# Power1.net
KiCad netlist of a schematic drawn in Altium Designer
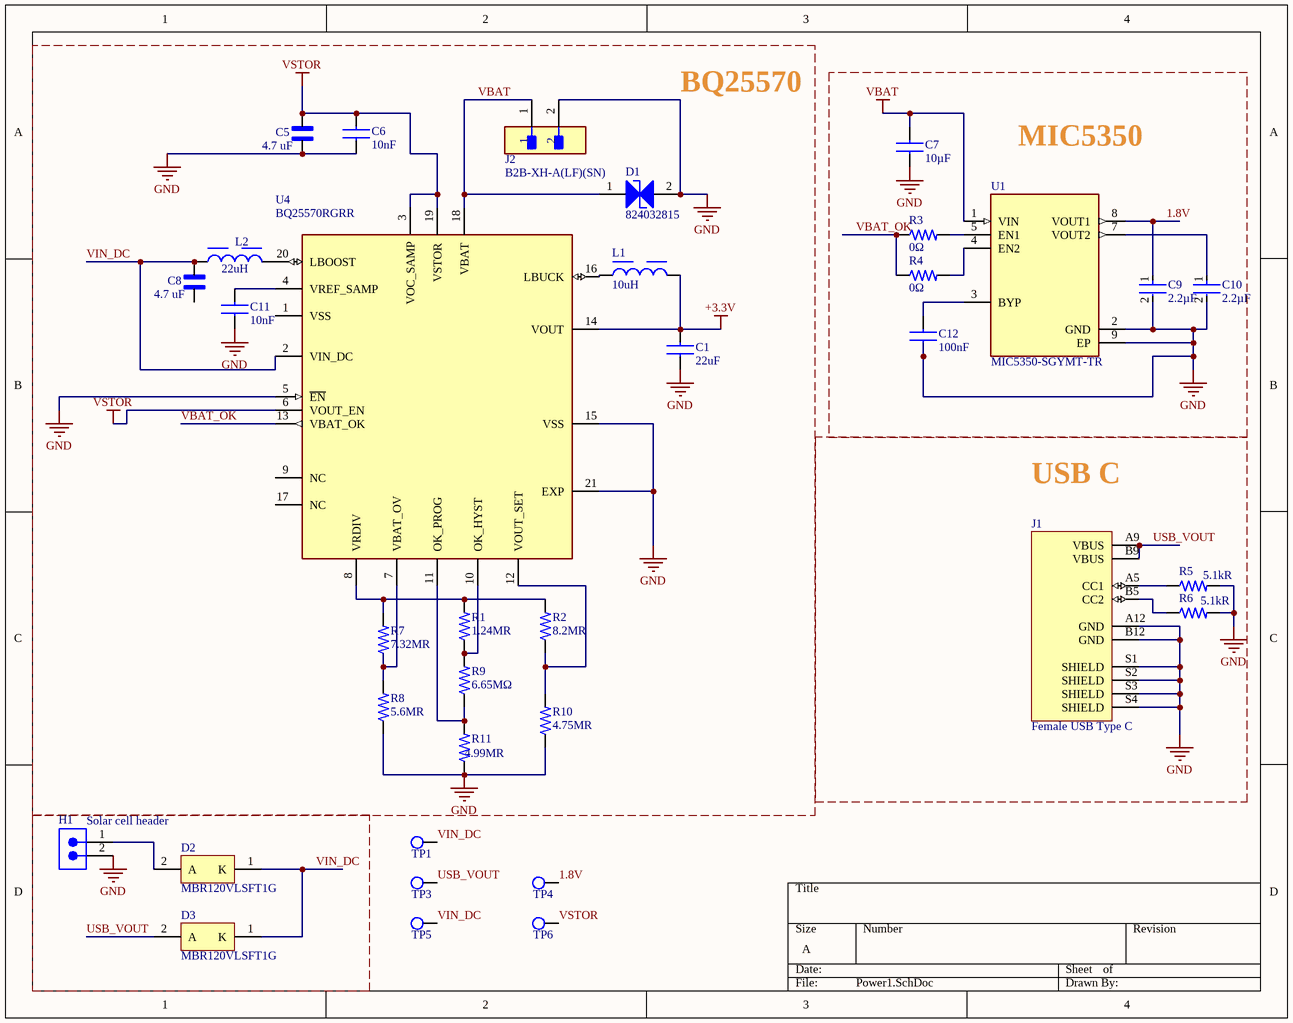
[diagram p0: Power1.SchDoc]

(export (version "E")
  (design (tool "Eeschema 10.0.6"))
  (components
    (comp (ref "C1")
      (value "22uF")
      (footprint "CAP_0603_1MM")
      (description "CAP CER 22UF 10V X5R 0603")
      (fields
        (field (name "MANUFACTURER") "Murata")
        (field (name "MANUFACTURER PART NUMBER") "GRM188R61A226ME15D")
      )
      (libsource (lib "LPEDT_Components") (part "GRM188R61A226ME15D"))
    )
    (comp (ref "C5")
      (value "4.7 uF")
      (footprint "CAPC1608X90N")
      (description "4.7 ÂµF Â±10% 16V Ceramic Capacitor X5R 0603 (1608 Metric)")
      (fields (field (name "MF") "Samsung Electro-Mechanics") (field (name "MP") "CL10A475KO8NNNC"))
      (libsource (lib "LPEDT_Components") (part "CL10A475KO8NNNC"))
    )
    (comp (ref "C6")
      (value "10nF")
      (footprint "CAP_0603_1MM")
      (description "Multilayer Ceramic Capacitors MLCC - SMD/SMT 16V 0.01uF X7R 0603 10% AEC-Q200")
      (fields
        (field (name "MANUFACTURER") "KEMET")
        (field (name "MANUFACTURER PART NUMBER") "C0603C103K4RECAUTO")
      )
      (libsource (lib "LPEDT_Components") (part "CAP 10nF 0603"))
    )
    (comp (ref "C7")
      (value "10µF")
      (footprint "CAP_0603_1MM")
      (description "10V 10uF X7R ±10% 0603 Multilayer Ceramic Capacitors MLCC - SMD/SMT ROHS")
      (fields
        (field (name "MANUFACTURER") "Murata")
        (field (name "MANUFACTURER PART NUMBER") "GRM188Z71A106KA73D")
      )
      (libsource (lib "LPEDT_Components") (part "CAP 10uF 0603"))
    )
    (comp (ref "C8")
      (value "4.7 uF")
      (footprint "CAPC1608X90N")
      (description "4.7 ÂµF Â±10% 16V Ceramic Capacitor X5R 0603 (1608 Metric)")
      (fields (field (name "MF") "Samsung Electro-Mechanics") (field (name "MP") "CL10A475KO8NNNC"))
      (libsource (lib "LPEDT_Components") (part "CL10A475KO8NNNC"))
    )
    (comp (ref "C9")
      (value "2.2µF")
      (footprint "CAP_0603_1MM")
      (description "10V 2.2uF X7R ±10% 0603 Multilayer Ceramic Capacitors MLCC - SMD/SMT ROHS")
      (fields
        (field (name "MANUFACTURER") "Samsung Electro-Mechanics")
        (field (name "MANUFACTURER PART NUMBER") "CL10B225KP8NNNC")
      )
      (libsource (lib "LPEDT_Components") (part "CAP 2.2uF 0603"))
    )
    (comp (ref "C10")
      (value "2.2µF")
      (footprint "CAP_0603_1MM")
      (description "10V 2.2uF X7R ±10% 0603 Multilayer Ceramic Capacitors MLCC - SMD/SMT ROHS")
      (fields
        (field (name "MANUFACTURER") "Samsung Electro-Mechanics")
        (field (name "MANUFACTURER PART NUMBER") "CL10B225KP8NNNC")
      )
      (libsource (lib "LPEDT_Components") (part "CAP 2.2uF 0603"))
    )
    (comp (ref "C11")
      (value "10nF")
      (footprint "CAP_0603_1MM")
      (description "Multilayer Ceramic Capacitors MLCC - SMD/SMT 16V 0.01uF X7R 0603 10% AEC-Q200")
      (fields
        (field (name "MANUFACTURER") "KEMET")
        (field (name "MANUFACTURER PART NUMBER") "C0603C103K4RECAUTO")
      )
      (libsource (lib "LPEDT_Components") (part "CAP 10nF 0603"))
    )
    (comp (ref "C12")
      (value "100nF")
      (footprint "CAP_0603_1MM")
      (description "0603 0.1 uF 10 V ±10% Tolerance X7R SMT Multilayer Ceramic Chip Capacitor")
      (fields
        (field (name "MANUFACTURER") "Vishay")
        (field (name "MANUFACTURER PART NUMBER") "VJ0603Y104KXQCW1BC")
      )
      (libsource (lib "LPEDT_Components") (part "CAP 0.1uF 0603"))
    )
    (comp (ref "D1")
      (value "824032815")
      (footprint "WE-TVS_DFN1610-2L")
      (description "824032815 Tvs Diode, Bidir, 5V, Dfn1610 Rohs Compliant: Yes ¦Wurth Elektronik 824032815")
      (libsource (lib "LPEDT_Components") (part "TVS Diode ESD Protection"))
    )
    (comp (ref "D2")
      (value "MBR120VLSFT1G")
      (footprint "ONSC-SOD-123FL-2-498-01_V")
      (description "Schottky Power Rectifier, 2-Pin SOD-123, Pb-Free, Tape and Reel")
      (fields (field (name "MANUFACTURER") "On Semiconductor"))
      (libsource (lib "LPEDT_Components") (part "Diode Schottky"))
    )
    (comp (ref "D3")
      (value "MBR120VLSFT1G")
      (footprint "ONSC-SOD-123FL-2-498-01_V")
      (description "Schottky Power Rectifier, 2-Pin SOD-123, Pb-Free, Tape and Reel")
      (fields (field (name "MANUFACTURER") "On Semiconductor"))
      (libsource (lib "LPEDT_Components") (part "Diode Schottky"))
    )
    (comp (ref "H1")
      (value "Solar cell header")
      (footprint "2-PIN_MALE_HEADER_01-IN")
      (description "CONN HEADER VERT 2POS 2.54MM")
      (fields
        (field (name "MANUFACTURER") "Sullins")
        (field (name "MANUFACTURER PART NUMBER") "PRPC002SAAN-RC")
      )
      (libsource (lib "LPEDT_Components") (part "SOLAR_CELL"))
    )
    (comp (ref "J1")
      (value "Female USB Type C")
      (footprint "GCT_USB4125-GF-A_REVA2")
      (fields (field (name "MANUFACTURER PART NUMBER") "USB4125-GF-A_REVA2"))
      (libsource (lib "LPEDT_Components") (part "USB-C Power Connector"))
    )
    (comp (ref "J2")
      (value "B2B-XH-A(LF)(SN)")
      (footprint "FP-B2B-XH-A_LF_SN-MFG")
      (description "CONN HEADER VERT 2POS 2.5MM")
      (libsource (lib "LPEDT_Components") (part "CMP-2000-05888-3"))
    )
    (comp (ref "L1")
      (value "10uH")
      (footprint "WE-TPC_2813")
      (description "10 µH Shielded Drum Core, Wirewound Inductor 650 mA 470mOhm Max Nonstandard")
      (fields (field (name "TOLERANCE") "30%"))
      (libsource (lib "LPEDT_Components") (part "CMP-0227-00077-3"))
    )
    (comp (ref "L2")
      (value "22uH")
      (footprint "WE-TPC_3816")
      (description "22 µH Shielded Drum Core, Wirewound Inductor 510 mA 450mOhm Max Nonstandard")
      (fields (field (name "TOLERANCE") "30%"))
      (libsource (lib "LPEDT_Components") (part "CMP-0227-00346-4"))
    )
    (comp (ref "R1")
      (value "1.24MR")
      (footprint "RES_0603_1608X06")
      (fields
        (field (name "MANUFACTURER") "Yageo")
        (field (name "MANUFACTURER PART NUMBER") "RC0603FR-071M24L")
        (field (name "TOLERANCE") "1%")
      )
      (libsource (lib "LPEDT_Component_Lib") (part "RES 1.24M 0603"))
    )
    (comp (ref "R2")
      (value "8.2MR")
      (footprint "RES_0603_1608X06")
      (fields
        (field (name "MANUFACTURER") "Yageo")
        (field (name "MANUFACTURER PART NUMBER") "RC0603JR-078M2L")
        (field (name "TOLERANCE") "5%")
      )
      (libsource (lib "LPEDT_Components") (part "RES 8.2M 0603"))
    )
    (comp (ref "R3")
      (value "0Ω")
      (footprint "RES_0603_1608X06")
      (description "GENERAL PURPOSE CHIP RESISTOR Metal Glaze/thick Film, 0.1W, 0ohm, Surface Mount, 0603")
      (fields
        (field (name "MANUFACTURER") "Yageo Group")
        (field (name "MANUFACTURER PART NUMBER") "RC0603JR-070RL")
      )
      (libsource (lib "LPEDT_Component_Lib") (part "RES 0R 0603"))
    )
    (comp (ref "R4")
      (value "0Ω")
      (footprint "RES_0603_1608X06")
      (description "GENERAL PURPOSE CHIP RESISTOR Metal Glaze/thick Film, 0.1W, 0ohm, Surface Mount, 0603")
      (fields
        (field (name "MANUFACTURER") "Yageo Group")
        (field (name "MANUFACTURER PART NUMBER") "RC0603JR-070RL")
      )
      (libsource (lib "LPEDT_Component_Lib") (part "RES 0R 0603"))
    )
    (comp (ref "R5")
      (value "5.1kR")
      (footprint "RES_0603_1608X06")
      (fields
        (field (name "MANUFACTURER") "Yageo")
        (field (name "MANUFACTURER PART NUMBER") "RC0603FR-075K1L")
        (field (name "TOLERANCE") "1%")
      )
      (libsource (lib "LPEDT_Component_Lib") (part "RES 5.1K 0603"))
    )
    (comp (ref "R6")
      (value "5.1kR")
      (footprint "RES_0603_1608X06")
      (fields
        (field (name "MANUFACTURER") "Yageo")
        (field (name "MANUFACTURER PART NUMBER") "RC0603FR-075K1L")
        (field (name "TOLERANCE") "1%")
      )
      (libsource (lib "LPEDT_Component_Lib") (part "RES 5.1K 0603"))
    )
    (comp (ref "R7")
      (value "7.32MR")
      (footprint "RES_0603_1608X06")
      (fields
        (field (name "MANUFACTURER") "Yageo")
        (field (name "MANUFACTURER PART NUMBER") "RC0402FR-077M32L")
        (field (name "TOLERANCE") "1%")
      )
      (libsource (lib "LPEDT_Component_Lib") (part "RES 7.32M 0603"))
    )
    (comp (ref "R8")
      (value "5.6MR")
      (footprint "RES_0603_1608X06")
      (fields
        (field (name "MANUFACTURER") "Yageo")
        (field (name "MANUFACTURER PART NUMBER") "RC0603JR-075M6L")
        (field (name "TOLERANCE") "5%")
      )
      (libsource (lib "LPEDT_Component_Lib") (part "RES 5.62M 0603"))
    )
    (comp (ref "R9")
      (value "6.65MΩ")
      (footprint "RES_0603_1608X06")
      (description "Res Thick Film 0603 6.65M Ohm 1% 0.1W(1/10W) ±200ppm/C Pad SMD T/R Automotive AEC-Q200")
      (fields
        (field (name "MANUFACTURER") "Stackpole Electronics")
        (field (name "MANUFACTURER PART NUMBER") "RMCF0603FT6M65")
      )
      (libsource (lib "LPEDT_Component_Lib") (part "RES 6.65M 0603"))
    )
    (comp (ref "R10")
      (value "4.75MR")
      (footprint "RES_0603_1608X06")
      (fields
        (field (name "MANUFACTURER") "Yageo")
        (field (name "MANUFACTURER PART NUMBER") "RC0603FR-074M75L")
        (field (name "TOLERANCE") "1%")
      )
      (libsource (lib "LPEDT_Components") (part "RES 4.75M 0603"))
    )
    (comp (ref "R11")
      (value "4.99MR")
      (footprint "RES_0603_1608X06")
      (fields
        (field (name "MANUFACTURER") "Yageo")
        (field (name "MANUFACTURER PART NUMBER") "RC0603FR-074M99L")
        (field (name "TOLERANCE") "1%")
      )
      (libsource (lib "LPEDT_Component_Lib") (part "RES 4.99M 0603"))
    )
    (comp (ref "TP1")
      (value "Test Point")
      (footprint "Test Point")
      (libsource (lib "LPEDT_Components") (part "Test Point"))
    )
    (comp (ref "TP3")
      (value "Test Point")
      (footprint "Test Point")
      (libsource (lib "LPEDT_Components") (part "Test Point"))
    )
    (comp (ref "TP4")
      (value "Test Point")
      (footprint "Test Point")
      (libsource (lib "LPEDT_Components") (part "Test Point"))
    )
    (comp (ref "TP5")
      (value "Test Point")
      (footprint "Test Point")
      (libsource (lib "LPEDT_Components") (part "Test Point"))
    )
    (comp (ref "TP6")
      (value "Test Point")
      (footprint "Test Point")
      (libsource (lib "LPEDT_Components") (part "Test Point"))
    )
    (comp (ref "U1")
      (value "MIC5350-SGYMT-TR")
      (footprint "SON50P200X200X60-9N")
      (description "Linear Voltage Regulator IC Positive Fixed 2 Output 300mA, 500mA 8-TMLFÂ® (2x2)")
      (fields (field (name "MF") "Microchip"))
      (libsource (lib "LPEDT_Components") (part "MIC5350-SGYMT-TR"))
    )
    (comp (ref "U4")
      (value "BQ25570RGRR")
      (footprint "QFN50P350X350X100-21N")
      (description "Ultra Low power Harvester power Management IC with boost charger, and Nanopower Buck Converter")
      (fields (field (name "MF") "Texas Instruments"))
      (libsource (lib "LPEDT_Components") (part "BQ25570RGRR"))
    )
  )
  (nets
    (net (code "1") (name "+3.3V") (class "Default")
      (node (ref "C1") (pin "2") (pinfunction "2_2") (pintype "passive"))
      (node (ref "L1") (pin "2") (pinfunction "2_2") (pintype "passive"))
      (node (ref "U4") (pin "14") (pinfunction "VOUT_14") (pintype "power_in"))
    )
    (net (code "2") (name "/1.8V") (class "Default")
      (node (ref "C9") (pin "1") (pinfunction "1_1") (pintype "passive"))
      (node (ref "TP4") (pin "1") (pinfunction "1_1") (pintype "passive"))
      (node (ref "U1") (pin "8") (pinfunction "VOUT1_8") (pintype "output"))
    )
    (net (code "4") (name "/USB_VOUT") (class "Default")
      (node (ref "D3") (pin "2") (pinfunction "A_2") (pintype "passive"))
      (node (ref "J1") (pin "A9") (pinfunction "VBUS_A9") (pintype "power_in"))
      (node (ref "TP3") (pin "1") (pinfunction "1_1") (pintype "passive"))
    )
    (net (code "5") (name "/VBAT_OK") (class "Default")
      (node (ref "R3") (pin "1") (pinfunction "1_1") (pintype "passive"))
      (node (ref "R4") (pin "1") (pinfunction "1_1") (pintype "passive"))
      (node (ref "U4") (pin "13") (pinfunction "VBAT_OK_13") (pintype "output"))
    )
    (net (code "6") (name "/VIN_DC") (class "Default")
      (node (ref "C8") (pin "2") (pinfunction "2_2") (pintype "passive"))
      (node (ref "D2") (pin "1") (pinfunction "K_1") (pintype "passive"))
      (node (ref "D3") (pin "1") (pinfunction "K_1") (pintype "passive"))
      (node (ref "L2") (pin "1") (pinfunction "1_1") (pintype "passive"))
      (node (ref "TP1") (pin "1") (pinfunction "1_1") (pintype "passive"))
      (node (ref "TP5") (pin "1") (pinfunction "1_1") (pintype "passive"))
      (node (ref "U4") (pin "2") (pinfunction "VIN_DC_2") (pintype "power_in"))
    )
    (net (code "7") (name "GND") (class "Default")
      (node (ref "C1") (pin "1") (pinfunction "1_1") (pintype "passive"))
      (node (ref "C10") (pin "2") (pinfunction "2_2") (pintype "passive"))
      (node (ref "C11") (pin "2") (pinfunction "2_2") (pintype "passive"))
      (node (ref "C12") (pin "2") (pinfunction "2_2") (pintype "passive"))
      (node (ref "C5") (pin "1") (pinfunction "1_1") (pintype "passive"))
      (node (ref "C6") (pin "2") (pinfunction "2_2") (pintype "passive"))
      (node (ref "C7") (pin "2") (pinfunction "2_2") (pintype "passive"))
      (node (ref "C9") (pin "2") (pinfunction "2_2") (pintype "passive"))
      (node (ref "D1") (pin "2") (pinfunction "GND_2") (pintype "passive"))
      (node (ref "H1") (pin "2") (pinfunction "2_2") (pintype "passive"))
      (node (ref "J1") (pin "A12") (pinfunction "GND_A12") (pintype "passive"))
      (node (ref "J1") (pin "B12") (pinfunction "GND_B12") (pintype "passive"))
      (node (ref "J1") (pin "S1") (pinfunction "SHIELD_S1") (pintype "passive"))
      (node (ref "J1") (pin "S2") (pinfunction "SHIELD_S2") (pintype "passive"))
      (node (ref "J1") (pin "S3") (pinfunction "SHIELD_S3") (pintype "passive"))
      (node (ref "J1") (pin "S4") (pinfunction "SHIELD_S4") (pintype "passive"))
      (node (ref "J2") (pin "2") (pinfunction "2_2") (pintype "passive"))
      (node (ref "R10") (pin "1") (pinfunction "1_1") (pintype "passive"))
      (node (ref "R11") (pin "1") (pinfunction "1_1") (pintype "passive"))
      (node (ref "R5") (pin "2") (pinfunction "2_2") (pintype "passive"))
      (node (ref "R6") (pin "2") (pinfunction "2_2") (pintype "passive"))
      (node (ref "R8") (pin "1") (pinfunction "1_1") (pintype "passive"))
      (node (ref "U1") (pin "2") (pinfunction "GND_2") (pintype "power_in"))
      (node (ref "U1") (pin "9") (pinfunction "EP_9") (pintype "power_in"))
      (node (ref "U4") (pin "15") (pinfunction "VSS_15") (pintype "power_in"))
      (node (ref "U4") (pin "21") (pinfunction "EXP_21") (pintype "passive"))
      (node (ref "U4") (pin "5") (pinfunction "~{EN}_5") (pintype "input"))
    )
    (net (code "8") (name "Net-(D2-A)") (class "Default")
      (node (ref "D2") (pin "2") (pinfunction "A_2") (pintype "passive"))
      (node (ref "H1") (pin "1") (pinfunction "1_1") (pintype "passive"))
    )
    (net (code "9") (name "Net-(J1-CC1)") (class "Default")
      (node (ref "J1") (pin "A5") (pinfunction "CC1_A5") (pintype "bidirectional"))
      (node (ref "R5") (pin "1") (pinfunction "1_1") (pintype "passive"))
    )
    (net (code "10") (name "Net-(J1-CC2)") (class "Default")
      (node (ref "J1") (pin "B5") (pinfunction "CC2_B5") (pintype "bidirectional"))
      (node (ref "R6") (pin "1") (pinfunction "1_1") (pintype "passive"))
    )
    (net (code "11") (name "Net-(U1-BYP)") (class "Default")
      (node (ref "C12") (pin "1") (pinfunction "1_1") (pintype "passive"))
      (node (ref "U1") (pin "3") (pinfunction "BYP_3") (pintype "passive"))
    )
    (net (code "12") (name "Net-(U1-EN1)") (class "Default")
      (node (ref "R3") (pin "2") (pinfunction "2_2") (pintype "passive"))
      (node (ref "U1") (pin "5") (pinfunction "EN1_5") (pintype "passive"))
    )
    (net (code "13") (name "Net-(U1-EN2)") (class "Default")
      (node (ref "R4") (pin "2") (pinfunction "2_2") (pintype "passive"))
      (node (ref "U1") (pin "4") (pinfunction "EN2_4") (pintype "passive"))
    )
    (net (code "14") (name "Net-(U1-VOUT2)") (class "Default")
      (node (ref "C10") (pin "1") (pinfunction "1_1") (pintype "passive"))
      (node (ref "U1") (pin "7") (pinfunction "VOUT2_7") (pintype "output"))
    )
    (net (code "15") (name "Net-(U4-LBOOST)") (class "Default")
      (node (ref "L2") (pin "2") (pinfunction "2_2") (pintype "passive"))
      (node (ref "U4") (pin "20") (pinfunction "LBOOST_20") (pintype "bidirectional"))
    )
    (net (code "16") (name "Net-(U4-LBUCK)") (class "Default")
      (node (ref "L1") (pin "1") (pinfunction "1_1") (pintype "passive"))
      (node (ref "U4") (pin "16") (pinfunction "LBUCK_16") (pintype "bidirectional"))
    )
    (net (code "17") (name "Net-(U4-OK_HYST)") (class "Default")
      (node (ref "R1") (pin "1") (pinfunction "1_1") (pintype "passive"))
      (node (ref "R9") (pin "2") (pinfunction "2_2") (pintype "passive"))
      (node (ref "U4") (pin "10") (pinfunction "OK_HYST_10") (pintype "passive"))
    )
    (net (code "18") (name "Net-(U4-OK_PROG)") (class "Default")
      (node (ref "R11") (pin "2") (pinfunction "2_2") (pintype "passive"))
      (node (ref "R9") (pin "1") (pinfunction "1_1") (pintype "passive"))
      (node (ref "U4") (pin "11") (pinfunction "OK_PROG_11") (pintype "passive"))
    )
    (net (code "19") (name "Net-(U4-VBAT_OV)") (class "Default")
      (node (ref "R7") (pin "1") (pinfunction "1_1") (pintype "passive"))
      (node (ref "R8") (pin "2") (pinfunction "2_2") (pintype "passive"))
      (node (ref "U4") (pin "7") (pinfunction "VBAT_OV_7") (pintype "passive"))
    )
    (net (code "20") (name "Net-(U4-VOUT_SET)") (class "Default")
      (node (ref "R10") (pin "2") (pinfunction "2_2") (pintype "passive"))
      (node (ref "R2") (pin "1") (pinfunction "1_1") (pintype "passive"))
      (node (ref "U4") (pin "12") (pinfunction "VOUT_SET_12") (pintype "passive"))
    )
    (net (code "21") (name "Net-(U4-VRDIV)") (class "Default")
      (node (ref "R1") (pin "2") (pinfunction "2_2") (pintype "passive"))
      (node (ref "R2") (pin "2") (pinfunction "2_2") (pintype "passive"))
      (node (ref "R7") (pin "2") (pinfunction "2_2") (pintype "passive"))
      (node (ref "U4") (pin "8") (pinfunction "VRDIV_8") (pintype "passive"))
    )
    (net (code "22") (name "Net-(U4-VREF_SAMP)") (class "Default")
      (node (ref "C11") (pin "1") (pinfunction "1_1") (pintype "passive"))
      (node (ref "U4") (pin "4") (pinfunction "VREF_SAMP_4") (pintype "power_in"))
    )
    (net (code "23") (name "VBAT") (class "Default")
      (node (ref "C7") (pin "1") (pinfunction "1_1") (pintype "passive"))
      (node (ref "D1") (pin "1") (pinfunction "I/O_1_1") (pintype "passive"))
      (node (ref "J2") (pin "1") (pinfunction "1_1") (pintype "passive"))
      (node (ref "U1") (pin "1") (pinfunction "VIN_1") (pintype "input"))
      (node (ref "U4") (pin "18") (pinfunction "VBAT_18") (pintype "power_in"))
    )
    (net (code "24") (name "VSTOR") (class "Default")
      (node (ref "C5") (pin "2") (pinfunction "2_2") (pintype "passive"))
      (node (ref "C6") (pin "1") (pinfunction "1_1") (pintype "passive"))
      (node (ref "TP6") (pin "1") (pinfunction "1_1") (pintype "passive"))
      (node (ref "U4") (pin "19") (pinfunction "VSTOR_19") (pintype "passive"))
      (node (ref "U4") (pin "3") (pinfunction "VOC_SAMP_3") (pintype "passive"))
      (node (ref "U4") (pin "6") (pinfunction "VOUT_EN_6") (pintype "passive"))
    )
    (net (code "25") (name "unconnected-(C8-Pad1)") (class "Default")
      (node (ref "C8") (pin "1") (pinfunction "1_1") (pintype "passive"))
    )
    (net (code "26") (name "unconnected-(J1-VBUS-PadB9)") (class "Default")
      (node (ref "J1") (pin "B9") (pinfunction "VBUS_B9") (pintype "power_in"))
    )
    (net (code "27") (name "unconnected-(U4-NC-Pad9)") (class "Default")
      (node (ref "U4") (pin "9") (pinfunction "NC_9") (pintype "passive"))
    )
    (net (code "28") (name "unconnected-(U4-NC-Pad17)") (class "Default")
      (node (ref "U4") (pin "17") (pinfunction "NC_17") (pintype "passive"))
    )
    (net (code "29") (name "unconnected-(U4-VSS-Pad1)") (class "Default")
      (node (ref "U4") (pin "1") (pinfunction "VSS_1") (pintype "power_in"))
    )
  )
)
